# circuit.net
KiCad netlist of a schematic drawn in Altium Designer
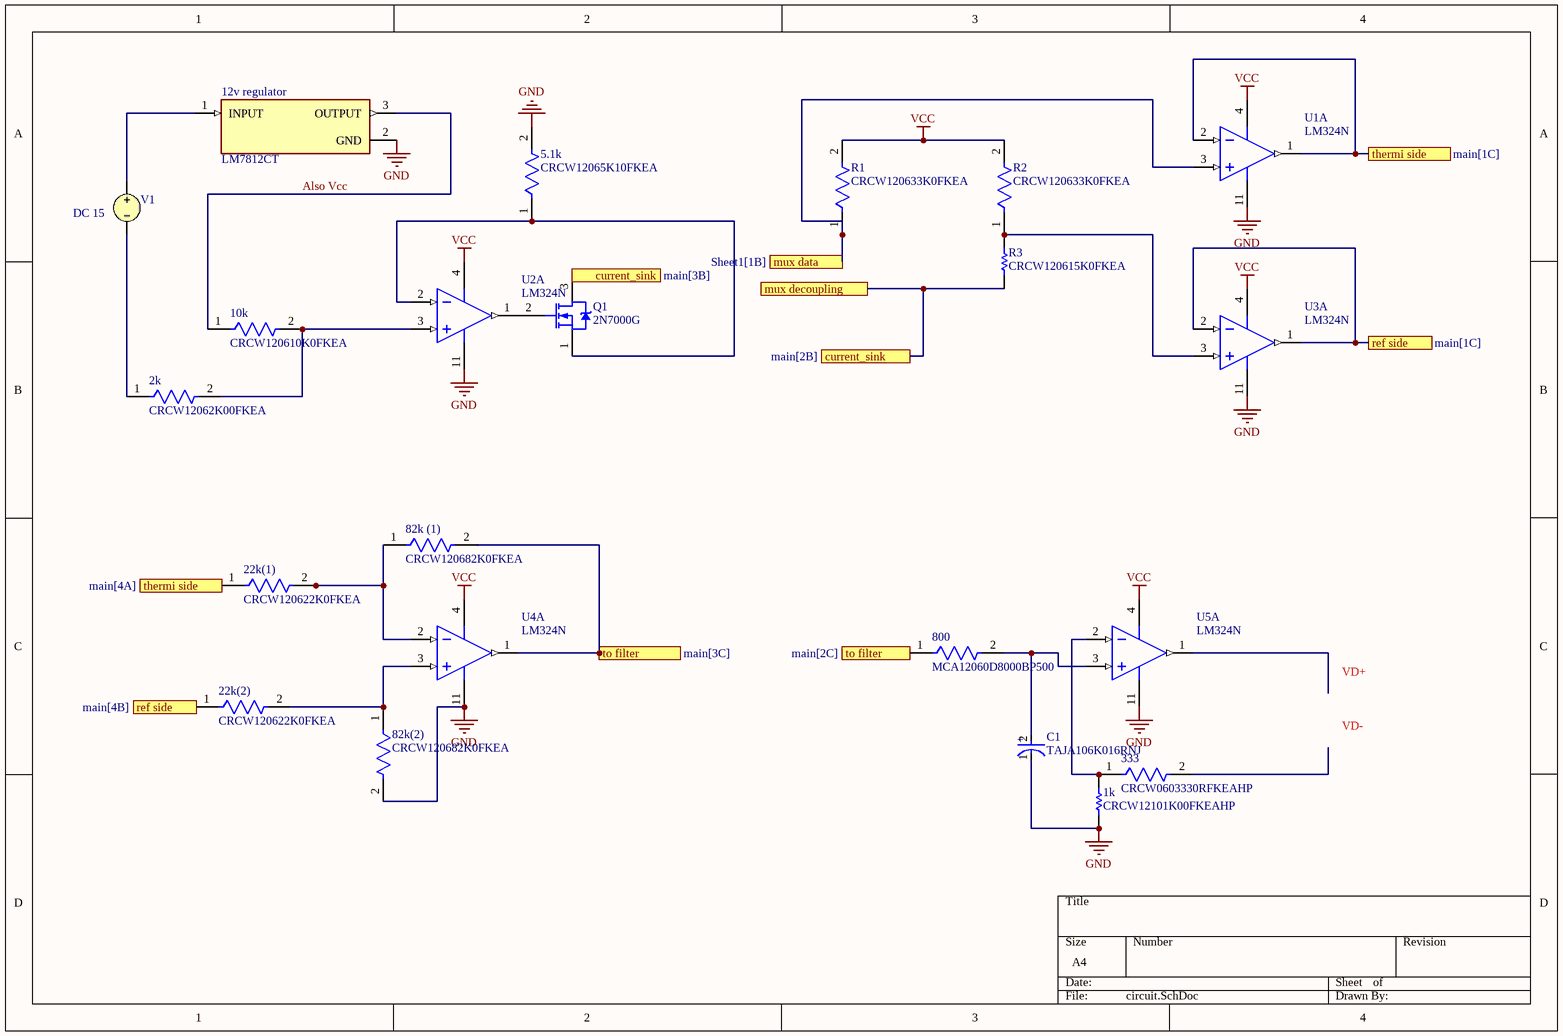
[diagram p0: circuit.SchDoc]

(export (version "E")
  (design (tool "Eeschema 10.0.6"))
  (components
    (comp (ref "1k")
      (value "CRCW12101K00FKEAHP")
      (footprint "RESC3225X60X45NL20T20")
      (fields (field (name "MANUFACTURER") "Vishay Dale"))
      (libsource (lib "Altium Content Vault") (part "RES"))
    )
    (comp (ref "2k")
      (value "CRCW12062K00FKEA")
      (footprint "FP-CRCW1206-e3-IPC_A")
      (description "RES Thick Film, 2kΩ, 1%, 0.25W, 100ppm/°C, 1206")
      (fields (field (name "TOLERANCE") "1%"))
      (libsource (lib "Altium Content Vault") (part "1029c3af85768c4190bb7ad29bc67b5"))
    )
    (comp (ref "5.1k")
      (value "CRCW12065K10FKEA")
      (footprint "FP-CRCW1206-e3-IPC_C")
      (description "RES Thick Film, 5.1kΩ, 1%, 0.25W, 100ppm/°C, 1206")
      (fields (field (name "TOLERANCE") "1%"))
      (libsource (lib "Altium Content Vault") (part "1029c3af85768c4190bb7ad29bc67b5"))
    )
    (comp (ref "10k")
      (value "CRCW120610K0FKEA")
      (footprint "FP-CRCW1206-e3-IPC_C")
      (description "RES Thick Film, 10kΩ, 1%, 0.25W, 100ppm/°C, 1206")
      (fields (field (name "TOLERANCE") "1%"))
      (libsource (lib "Altium Content Vault") (part "1029c3af85768c4190bb7ad29bc67b5"))
    )
    (comp (ref "12v regulator")
      (value "LM7812CT")
      (footprint "FP-TO220B03-MFG")
      (description "IC REG LINEAR 12V 1A TO220-3")
      (fields
        (field (name "OCTOPART") "https://octopart.com/lm7812ct-on+semiconductor-14383031")
        (field (name "OBSOLETE PART") "true")
      )
      (libsource (lib "Altium Content Vault") (part "6207a8f1a6b4db326a9e0a8a99b4969"))
    )
    (comp (ref "22k(1)")
      (value "CRCW120622K0FKEA")
      (footprint "FP-CRCW1206-e3-IPC_A")
      (description "RES Thick Film, 22kΩ, 1%, 0.25W, 100ppm/°C, 1206")
      (fields (field (name "TOLERANCE") "1%"))
      (libsource (lib "Altium Content Vault") (part "1029c3af85768c4190bb7ad29bc67b5"))
    )
    (comp (ref "22k(2)")
      (value "CRCW120622K0FKEA")
      (footprint "FP-CRCW1206-e3-IPC_A")
      (description "RES Thick Film, 22kΩ, 1%, 0.25W, 100ppm/°C, 1206")
      (fields (field (name "TOLERANCE") "1%"))
      (libsource (lib "Altium Content Vault") (part "1029c3af85768c4190bb7ad29bc67b5"))
    )
    (comp (ref "82k (1)")
      (value "CRCW120682K0FKEA")
      (footprint "FP-CRCW1206-e3-IPC_B")
      (description "RES Thick Film, 82kΩ, 1%, 0.25W, 100ppm/°C, 1206")
      (fields (field (name "TOLERANCE") "1%"))
      (libsource (lib "Altium Content Vault") (part "1029c3af85768c4190bb7ad29bc67b5"))
    )
    (comp (ref "82k(2)")
      (value "CRCW120682K0FKEA")
      (footprint "FP-CRCW1206-e3-IPC_B")
      (description "RES Thick Film, 82kΩ, 1%, 0.25W, 100ppm/°C, 1206")
      (fields (field (name "TOLERANCE") "1%"))
      (libsource (lib "Altium Content Vault") (part "1029c3af85768c4190bb7ad29bc67b5"))
    )
    (comp (ref "333")
      (value "CRCW0603330RFKEAHP")
      (footprint "FP-CRCW0603-HPe3-IPC_C")
      (description "RES Thick Film, 330Ω, 1%, 0.33W, 100ppm/°C, 0603")
      (fields (field (name "TOLERANCE") "1%"))
      (libsource (lib "Altium Content Vault") (part "1029c3af85768c4190bb7ad29bc67b5"))
    )
    (comp (ref "800")
      (value "MCA12060D8000BP500")
      (footprint "FP-MCA1206-IPC_C")
      (description "Res MC Precision Thin Film 1206 800Ω 0.1% 0.25W ±25ppm/°C Molded Paper T/R")
      (fields (field (name "TOLERANCE") "0.1%"))
      (libsource (lib "Altium Content Vault") (part "1029c3af85768c4190bb7ad29bc67b5"))
    )
    (comp (ref "C1")
      (value "TAJA106K016RNJ")
      (footprint "FP-TAJA-MFG")
      (description "10uF 16V  ±10% 3Ω 1206  SMD Tantalum Capacitor")
      (fields (field (name "VOLTAGE") "16V") (field (name "TOLERANCE") "10%"))
      (libsource (lib "Altium Content Vault") (part "203bc49f2ac43e59fd269a8c329ed05"))
    )
    (comp (ref "Q1")
      (value "2N7000G")
      (footprint "ONSC-TO-92-3-29-11")
      (description "Small Signal MOSFET, 200 mA, 60 V, N-Channel, 3-Pin TO-92, Pb-Free, Bulk Box")
      (fields (field (name "MANUFACTURER") "On Semiconductor"))
      (libsource (lib "Altium Content Vault") (part "ONSC-NMOS-S1G2D3-3"))
    )
    (comp (ref "R1")
      (value "CRCW120633K0FKEA")
      (footprint "FP-CRCW1206-e3-IPC_B")
      (description "RES Thick Film, 33kΩ, 1%, 0.25W, 100ppm/°C, 1206")
      (fields (field (name "TOLERANCE") "1%"))
      (libsource (lib "Altium Content Vault") (part "1029c3af85768c4190bb7ad29bc67b5"))
    )
    (comp (ref "R2")
      (value "CRCW120633K0FKEA")
      (footprint "FP-CRCW1206-e3-IPC_B")
      (description "RES Thick Film, 33kΩ, 1%, 0.25W, 100ppm/°C, 1206")
      (fields (field (name "TOLERANCE") "1%"))
      (libsource (lib "Altium Content Vault") (part "1029c3af85768c4190bb7ad29bc67b5"))
    )
    (comp (ref "R3")
      (value "CRCW120615K0FKEA")
      (footprint "RESC3216X60X45LL10T20")
      (fields (field (name "MANUFACTURER") "Vishay Dale"))
      (libsource (lib "Altium Content Vault") (part "RES"))
    )
    (comp (ref "U1")
      (value "LM324N")
      (footprint "N0014A")
      (description "Low Power Quad Operational Amplifier, 14-pin MDIP")
      (fields (field (name "MANUFACTURER") "Texas Instruments"))
      (libsource (lib "Altium Content Vault") (part "AMP-OPA-LM124-14"))
    )
    (comp (ref "U2")
      (value "LM324N")
      (footprint "N0014A")
      (description "Low Power Quad Operational Amplifier, 14-pin MDIP")
      (fields (field (name "MANUFACTURER") "Texas Instruments"))
      (libsource (lib "Altium Content Vault") (part "AMP-OPA-LM124-14"))
    )
    (comp (ref "U3")
      (value "LM324N")
      (footprint "N0014A")
      (description "Low Power Quad Operational Amplifier, 14-pin MDIP")
      (fields (field (name "MANUFACTURER") "Texas Instruments"))
      (libsource (lib "Altium Content Vault") (part "AMP-OPA-LM124-14"))
    )
    (comp (ref "U4")
      (value "LM324N")
      (footprint "N0014A")
      (description "Low Power Quad Operational Amplifier, 14-pin MDIP")
      (fields (field (name "MANUFACTURER") "Texas Instruments"))
      (libsource (lib "Altium Content Vault") (part "AMP-OPA-LM124-14"))
    )
    (comp (ref "U5")
      (value "LM324N")
      (footprint "N0014A")
      (description "Low Power Quad Operational Amplifier, 14-pin MDIP")
      (fields (field (name "MANUFACTURER") "Texas Instruments"))
      (libsource (lib "Altium Content Vault") (part "AMP-OPA-LM124-14"))
    )
    (comp (ref "V1")
      (value "DC 15")
      (description "Voltage Source")
      (fields (field (name "PUBLISHER") "Altium Limited"))
      (libsource (lib "Simulation Generic Components") (part "VSRC"))
    )
  )
  (nets
    (net (code "1") (name "/Also Vcc") (class "Default")
      (node (ref "10k") (pin "1") (pinfunction "1_1") (pintype "passive"))
      (node (ref "12v regulator") (pin "3") (pinfunction "OUTPUT_3") (pintype "output"))
    )
    (net (code "2") (name "/current_sink") (class "Default")
      (node (ref "Q1") (pin "3") (pinfunction "D_3") (pintype "passive"))
      (node (ref "R3") (pin "1") (pinfunction "1_1") (pintype "passive"))
    )
    (net (code "3") (name "/mux data") (class "Default")
      (node (ref "R1") (pin "1") (pinfunction "1_1") (pintype "passive"))
      (node (ref "U1") (pin "3") (pinfunction "IN1+_3") (pintype "input"))
    )
    (net (code "4") (name "/ref side") (class "Default")
      (node (ref "22k(2)") (pin "1") (pinfunction "1_1") (pintype "passive"))
      (node (ref "U3") (pin "1") (pinfunction "OUT1_1") (pintype "output"))
      (node (ref "U3") (pin "2") (pinfunction "IN1-_2") (pintype "input"))
    )
    (net (code "5") (name "/thermi side") (class "Default")
      (node (ref "22k(1)") (pin "1") (pinfunction "1_1") (pintype "passive"))
      (node (ref "U1") (pin "1") (pinfunction "OUT1_1") (pintype "output"))
      (node (ref "U1") (pin "2") (pinfunction "IN1-_2") (pintype "input"))
    )
    (net (code "6") (name "/to filter") (class "Default")
      (node (ref "800") (pin "1") (pinfunction "1_1") (pintype "passive"))
      (node (ref "82k (1)") (pin "2") (pinfunction "2_2") (pintype "passive"))
      (node (ref "U4") (pin "1") (pinfunction "OUT1_1") (pintype "output"))
    )
    (net (code "7") (name "GND") (class "Default")
      (node (ref "12v regulator") (pin "2") (pinfunction "GND_2") (pintype "power_in"))
      (node (ref "1k") (pin "1") (pinfunction "1_1") (pintype "passive"))
      (node (ref "5.1k") (pin "2") (pinfunction "2_2") (pintype "passive"))
      (node (ref "82k(2)") (pin "2") (pinfunction "2_2") (pintype "passive"))
      (node (ref "C1") (pin "1") (pinfunction "C_1") (pintype "passive"))
      (node (ref "U1") (pin "11") (pinfunction "GND_11") (pintype "power_in"))
      (node (ref "U2") (pin "11") (pinfunction "GND_11") (pintype "power_in"))
      (node (ref "U3") (pin "11") (pinfunction "GND_11") (pintype "power_in"))
      (node (ref "U4") (pin "11") (pinfunction "GND_11") (pintype "power_in"))
      (node (ref "U5") (pin "11") (pinfunction "GND_11") (pintype "power_in"))
    )
    (net (code "8") (name "Net-(2k-Pad1)") (class "Default")
      (node (ref "2k") (pin "1") (pinfunction "1_1") (pintype "passive"))
      (node (ref "V1") (pin "2") (pinfunction "2_2") (pintype "passive"))
    )
    (net (code "9") (name "Net-(12v regulator-INPUT)") (class "Default")
      (node (ref "12v regulator") (pin "1") (pinfunction "INPUT_1") (pintype "input"))
      (node (ref "V1") (pin "1") (pinfunction "1_1") (pintype "passive"))
    )
    (net (code "10") (name "Net-(C1-A)") (class "Default")
      (node (ref "800") (pin "2") (pinfunction "2_2") (pintype "passive"))
      (node (ref "C1") (pin "2") (pinfunction "A_2") (pintype "passive"))
      (node (ref "U5") (pin "3") (pinfunction "IN1+_3") (pintype "input"))
    )
    (net (code "11") (name "Net-(Q1-G)") (class "Default")
      (node (ref "Q1") (pin "2") (pinfunction "G_2") (pintype "passive"))
      (node (ref "U2") (pin "1") (pinfunction "OUT1_1") (pintype "output"))
    )
    (net (code "12") (name "Net-(Q1-S)") (class "Default")
      (node (ref "5.1k") (pin "1") (pinfunction "1_1") (pintype "passive"))
      (node (ref "Q1") (pin "1") (pinfunction "S_1") (pintype "passive"))
      (node (ref "U2") (pin "2") (pinfunction "IN1-_2") (pintype "input"))
    )
    (net (code "13") (name "Net-(U2A-IN1+)") (class "Default")
      (node (ref "10k") (pin "2") (pinfunction "2_2") (pintype "passive"))
      (node (ref "2k") (pin "2") (pinfunction "2_2") (pintype "passive"))
      (node (ref "U2") (pin "3") (pinfunction "IN1+_3") (pintype "input"))
    )
    (net (code "14") (name "Net-(U3A-IN1+)") (class "Default")
      (node (ref "R2") (pin "1") (pinfunction "1_1") (pintype "passive"))
      (node (ref "R3") (pin "2") (pinfunction "2_2") (pintype "passive"))
      (node (ref "U3") (pin "3") (pinfunction "IN1+_3") (pintype "input"))
    )
    (net (code "15") (name "Net-(U4A-IN1+)") (class "Default")
      (node (ref "22k(2)") (pin "2") (pinfunction "2_2") (pintype "passive"))
      (node (ref "82k(2)") (pin "1") (pinfunction "1_1") (pintype "passive"))
      (node (ref "U4") (pin "3") (pinfunction "IN1+_3") (pintype "input"))
    )
    (net (code "16") (name "Net-(U4A-IN1-)") (class "Default")
      (node (ref "22k(1)") (pin "2") (pinfunction "2_2") (pintype "passive"))
      (node (ref "82k (1)") (pin "1") (pinfunction "1_1") (pintype "passive"))
      (node (ref "U4") (pin "2") (pinfunction "IN1-_2") (pintype "input"))
    )
    (net (code "17") (name "Net-(U5A-IN1-)") (class "Default")
      (node (ref "1k") (pin "2") (pinfunction "2_2") (pintype "passive"))
      (node (ref "333") (pin "1") (pinfunction "1_1") (pintype "passive"))
      (node (ref "U5") (pin "2") (pinfunction "IN1-_2") (pintype "input"))
    )
    (net (code "18") (name "VCC") (class "Default")
      (node (ref "R1") (pin "2") (pinfunction "2_2") (pintype "passive"))
      (node (ref "R2") (pin "2") (pinfunction "2_2") (pintype "passive"))
      (node (ref "U1") (pin "4") (pinfunction "V+_4") (pintype "power_in"))
      (node (ref "U2") (pin "4") (pinfunction "V+_4") (pintype "power_in"))
      (node (ref "U3") (pin "4") (pinfunction "V+_4") (pintype "power_in"))
      (node (ref "U4") (pin "4") (pinfunction "V+_4") (pintype "power_in"))
      (node (ref "U5") (pin "4") (pinfunction "V+_4") (pintype "power_in"))
    )
    (net (code "19") (name "unconnected-(333-Pad2)") (class "Default")
      (node (ref "333") (pin "2") (pinfunction "2_2") (pintype "passive"))
    )
    (net (code "20") (name "unconnected-(U5A-OUT1-Pad1)") (class "Default")
      (node (ref "U5") (pin "1") (pinfunction "OUT1_1") (pintype "output"))
    )
  )
)
